# Calunium_PSU_v1.net
KiCad netlist of a schematic drawn in EAGLE
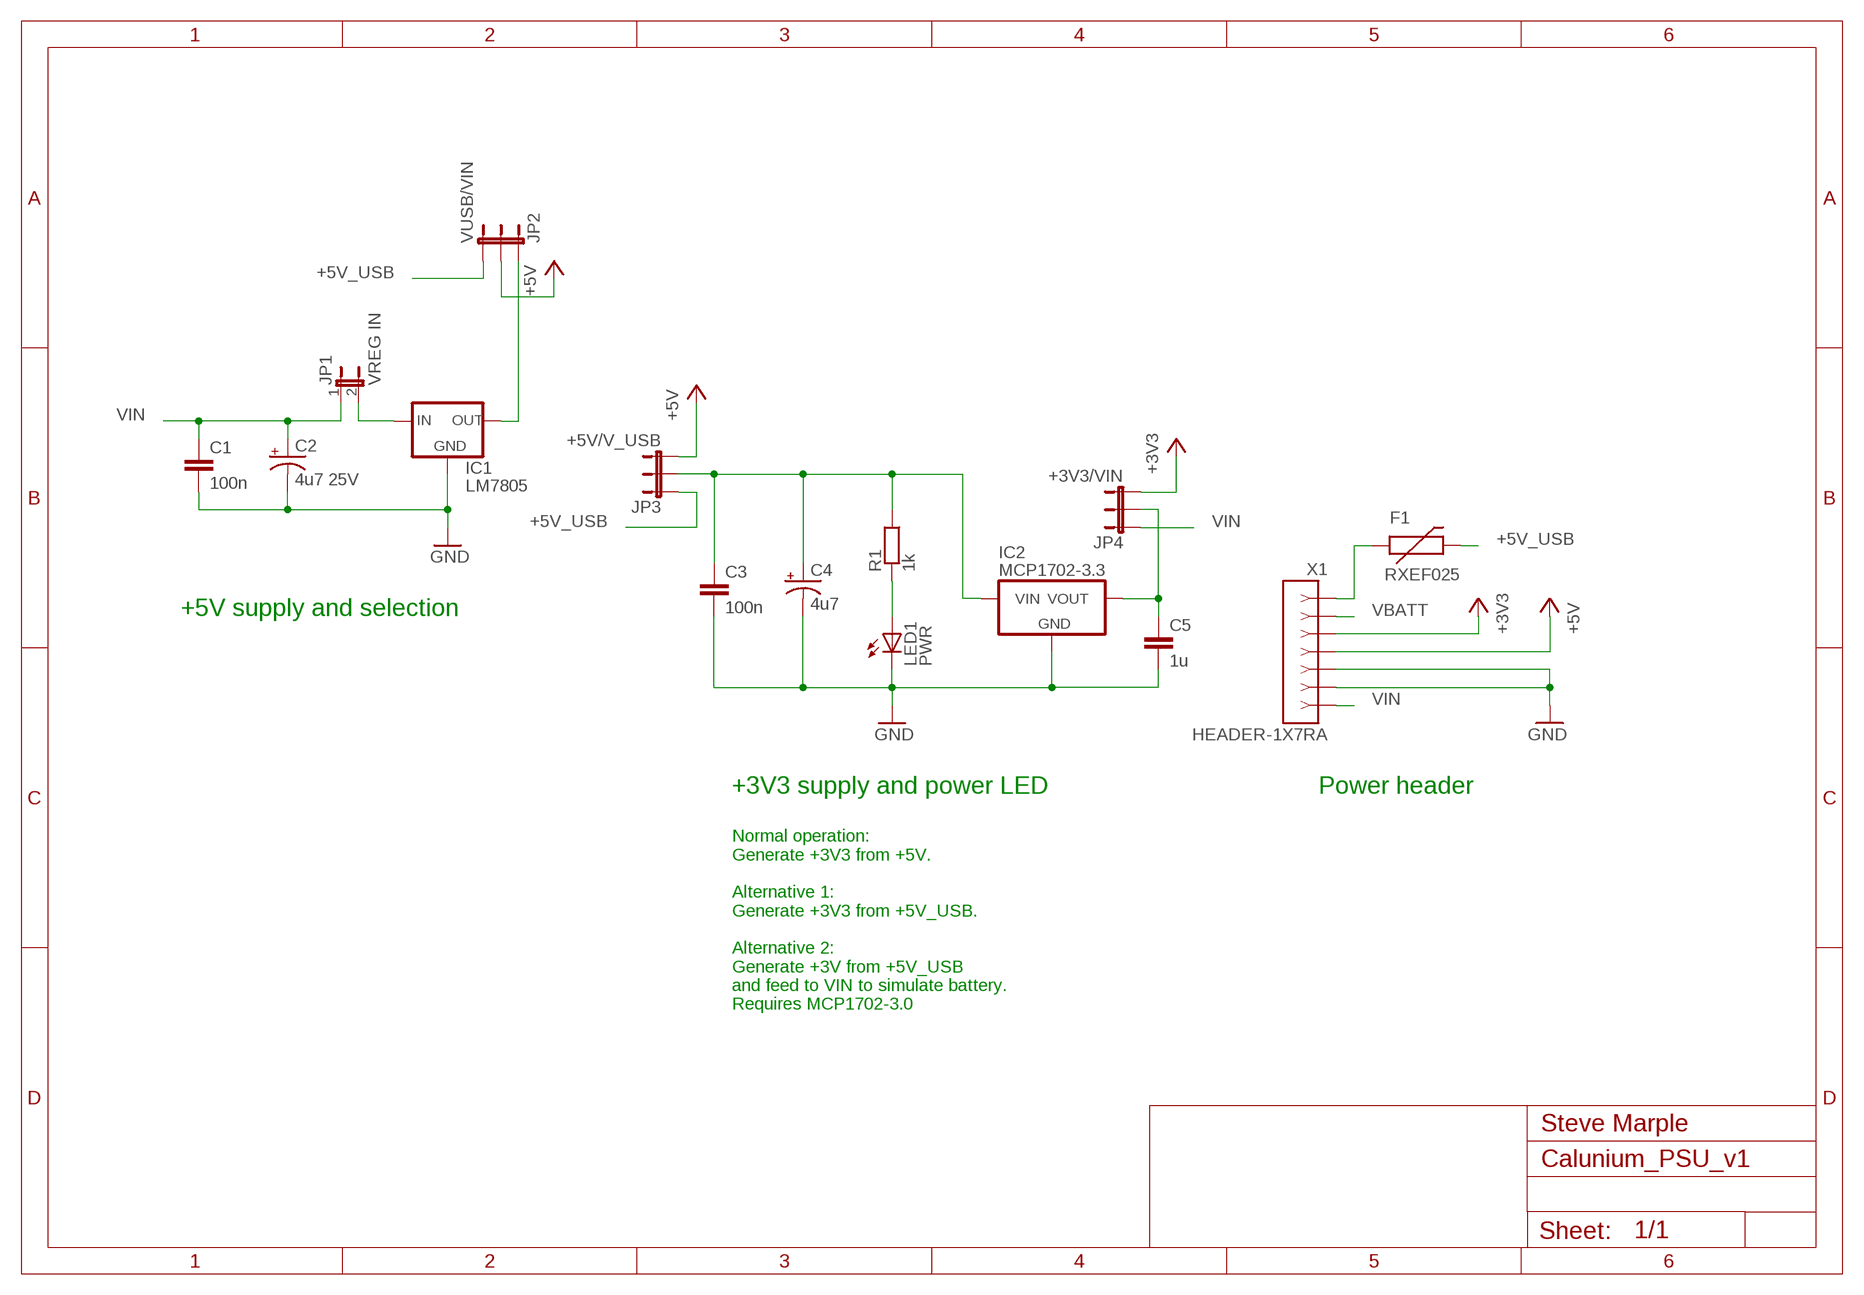
[diagram p0: schematic, sheet 1]

(export (version "E")
  (design (tool "Eeschema 10.0.6"))
  (components
    (comp (ref "C1")
      (value "100n")
      (footprint "eagle-import:CAP-PTH-SMALL")
      (libsource (lib "eagle-import") (part "CAPPTH"))
    )
    (comp (ref "C2")
      (value "4u7 25V")
      (footprint "eagle-import:CPOL-RADIAL-10UF-25V")
      (libsource (lib "eagle-import") (part "CAP_POLPTH2"))
    )
    (comp (ref "C3")
      (value "100n")
      (footprint "eagle-import:CAP-PTH-SMALL")
      (libsource (lib "eagle-import") (part "CAPPTH"))
    )
    (comp (ref "C4")
      (value "4u7")
      (footprint "eagle-import:CPOL-RADIAL-10UF-25V")
      (libsource (lib "eagle-import") (part "CAP_POLPTH2"))
    )
    (comp (ref "C5")
      (value "1u")
      (footprint "eagle-import:CAP-PTH-5MM")
      (libsource (lib "eagle-import") (part "CAPPTH1"))
    )
    (comp (ref "F1")
      (value "RXEF025")
      (footprint "eagle-import:PTC")
      (libsource (lib "eagle-import") (part "PTCPTH"))
    )
    (comp (ref "IC1")
      (value "LM7805")
      (footprint "eagle-import:78XXL-NO-HOLE")
      (libsource (lib "eagle-import") (part "V_REG_78XXSIDE-NO-HOLE"))
    )
    (comp (ref "IC2")
      (value "MCP1702-3.3")
      (footprint "eagle-import:TO-92")
      (libsource (lib "eagle-import") (part "MCP1702"))
    )
    (comp (ref "JP1")
      (value "VREG IN")
      (footprint "eagle-import:1X02")
      (libsource (lib "eagle-import") (part "JUMPER-2PTH"))
    )
    (comp (ref "JP2")
      (value "VUSB/VIN")
      (footprint "eagle-import:1X03")
      (libsource (lib "eagle-import") (part "JUMPER-3PTH"))
    )
    (comp (ref "JP3")
      (value "+5V/V_USB")
      (footprint "eagle-import:SJ_3")
      (libsource (lib "eagle-import") (part "JUMPER-3SMD"))
    )
    (comp (ref "JP4")
      (value "+3V3/VIN")
      (footprint "eagle-import:SJ_3")
      (libsource (lib "eagle-import") (part "JUMPER-3SMD"))
    )
    (comp (ref "LED1")
      (value "PWR")
      (footprint "eagle-import:LED3MM")
      (libsource (lib "eagle-import") (part "LED3MM"))
    )
    (comp (ref "R1")
      (value "1k")
      (footprint "eagle-import:RES-AXIAL-0.4")
      (libsource (lib "eagle-import") (part "RESISTOR"))
    )
    (comp (ref "X1")
      (value "HEADER-1X7RA")
      (footprint "eagle-import:HEADER-1X7-RA")
      (libsource (lib "eagle-import") (part "HEADER-1X7RA"))
    )
  )
  (nets
    (net (code "1") (name "+3V3") (class "Default")
      (node (ref "JP4") (pin "3") (pinfunction "3_3") (pintype "passive"))
      (node (ref "X1") (pin "3") (pinfunction "P$3_3") (pintype "bidirectional"))
    )
    (net (code "2") (name "+5V") (class "Default")
      (node (ref "JP2") (pin "2") (pinfunction "2_2") (pintype "passive"))
      (node (ref "JP3") (pin "3") (pinfunction "3_3") (pintype "passive"))
      (node (ref "X1") (pin "4") (pinfunction "P$4_4") (pintype "bidirectional"))
    )
    (net (code "3") (name "/+5V_USB") (class "Default")
      (node (ref "F1") (pin "P$2") (pinfunction "2_P$2") (pintype "bidirectional"))
      (node (ref "JP2") (pin "3") (pinfunction "3_3") (pintype "passive"))
      (node (ref "JP3") (pin "1") (pinfunction "1_1") (pintype "passive"))
    )
    (net (code "4") (name "/VBATT") (class "Default")
      (node (ref "X1") (pin "2") (pinfunction "P$2_2") (pintype "bidirectional"))
    )
    (net (code "5") (name "/VIN") (class "Default")
      (node (ref "C1") (pin "1") (pinfunction "1_1") (pintype "passive"))
      (node (ref "C2") (pin "1") (pinfunction "+_1") (pintype "passive"))
      (node (ref "JP1") (pin "1") (pinfunction "1_1") (pintype "passive"))
      (node (ref "JP4") (pin "1") (pinfunction "1_1") (pintype "passive"))
      (node (ref "X1") (pin "7") (pinfunction "P$7_7") (pintype "bidirectional"))
    )
    (net (code "6") (name "GND") (class "Default")
      (node (ref "C1") (pin "2") (pinfunction "2_2") (pintype "passive"))
      (node (ref "C2") (pin "2") (pinfunction "-_2") (pintype "passive"))
      (node (ref "C3") (pin "2") (pinfunction "2_2") (pintype "passive"))
      (node (ref "C4") (pin "2") (pinfunction "-_2") (pintype "passive"))
      (node (ref "C5") (pin "2") (pinfunction "2_2") (pintype "passive"))
      (node (ref "IC1") (pin "GND") (pinfunction "GND_GND") (pintype "power_in"))
      (node (ref "IC2") (pin "1") (pinfunction "GND_1") (pintype "passive"))
      (node (ref "LED1") (pin "K") (pinfunction "C_K") (pintype "passive"))
      (node (ref "X1") (pin "5") (pinfunction "P$5_5") (pintype "bidirectional"))
      (node (ref "X1") (pin "6") (pinfunction "P$6_6") (pintype "bidirectional"))
    )
    (net (code "7") (name "Net-(C4-+)") (class "Default")
      (node (ref "C3") (pin "1") (pinfunction "1_1") (pintype "passive"))
      (node (ref "C4") (pin "1") (pinfunction "+_1") (pintype "passive"))
      (node (ref "IC2") (pin "2") (pinfunction "VIN_2") (pintype "input"))
      (node (ref "JP3") (pin "2") (pinfunction "2_2") (pintype "passive"))
      (node (ref "R1") (pin "P$2") (pinfunction "2_P$2") (pintype "passive"))
    )
    (net (code "8") (name "Net-(F1-1)") (class "Default")
      (node (ref "F1") (pin "P$1") (pinfunction "1_P$1") (pintype "bidirectional"))
      (node (ref "X1") (pin "1") (pinfunction "P$1_1") (pintype "bidirectional"))
    )
    (net (code "9") (name "Net-(IC1-PadIN)") (class "Default")
      (node (ref "IC1") (pin "IN") (pinfunction "IN_IN") (pintype "input"))
      (node (ref "JP1") (pin "2") (pinfunction "2_2") (pintype "passive"))
    )
    (net (code "10") (name "Net-(IC1-PadOUT)") (class "Default")
      (node (ref "IC1") (pin "OUT") (pinfunction "OUT_OUT") (pintype "power_in"))
      (node (ref "JP2") (pin "1") (pinfunction "1_1") (pintype "passive"))
    )
    (net (code "11") (name "Net-(IC2-VOUT)") (class "Default")
      (node (ref "C5") (pin "1") (pinfunction "1_1") (pintype "passive"))
      (node (ref "IC2") (pin "3") (pinfunction "VOUT_3") (pintype "passive"))
      (node (ref "JP4") (pin "2") (pinfunction "2_2") (pintype "passive"))
    )
    (net (code "12") (name "Net-(R1-1)") (class "Default")
      (node (ref "LED1") (pin "A") (pinfunction "A_A") (pintype "passive"))
      (node (ref "R1") (pin "P$1") (pinfunction "1_P$1") (pintype "passive"))
    )
  )
)
